# Pi-XO.net
KiCad netlist of a schematic drawn in EAGLE
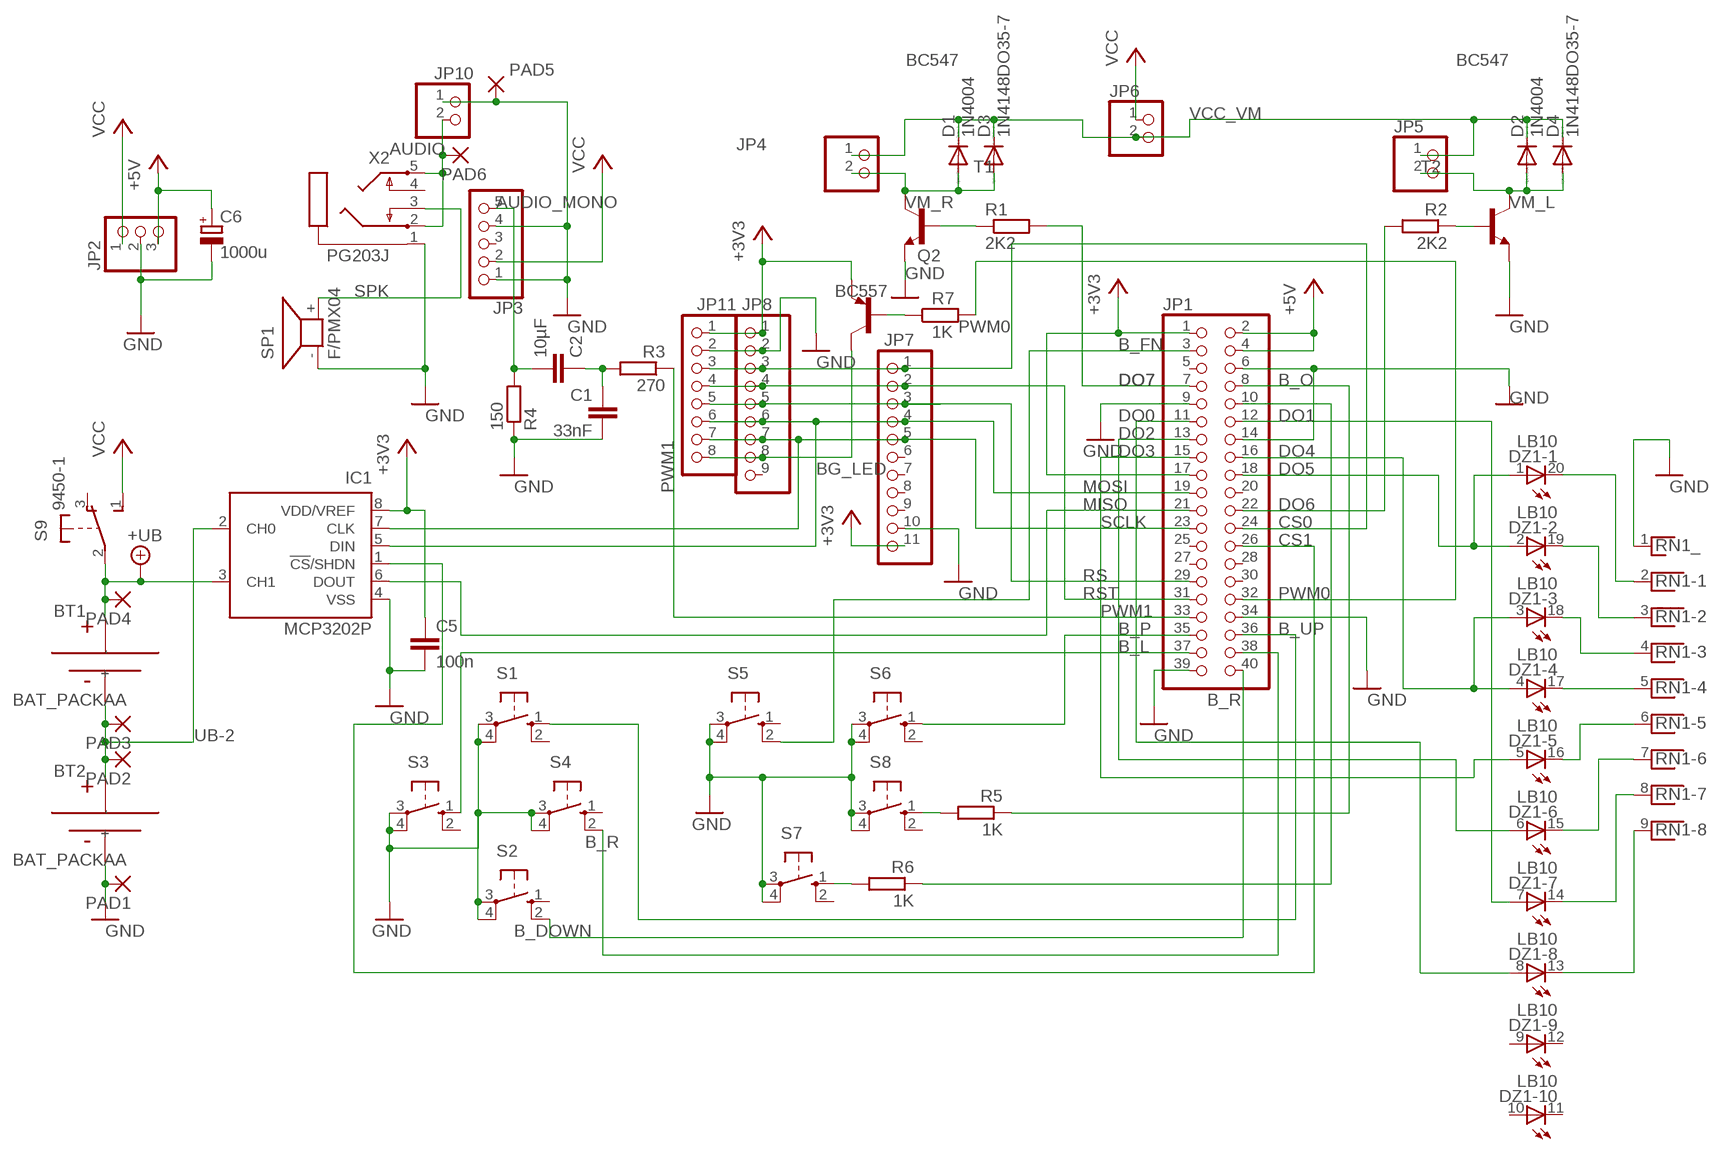
[diagram p0: schematic, sheet 1]

(export (version "E")
  (design (tool "Eeschema 10.0.6"))
  (components
    (comp (ref "BT1")
      (value "BAT_PACKAA")
      (footprint "eagle-import:BHAA-3")
      (fields (field (name "MANUFACTURER") "MPD") (field (name "MPN") "BHAA-3"))
      (libsource (lib "eagle-import") (part "BAT_PACKAA"))
    )
    (comp (ref "BT2")
      (value "BAT_PACKAA")
      (footprint "eagle-import:BHAA-3")
      (fields (field (name "MANUFACTURER") "MPD") (field (name "MPN") "BHAA-3"))
      (libsource (lib "eagle-import") (part "BAT_PACKAA"))
    )
    (comp (ref "C1")
      (value "33nF")
      (footprint "eagle-import:C050-024X044")
      (libsource (lib "eagle-import") (part "C-EU050-024X044"))
    )
    (comp (ref "C2")
      (value "10µF")
      (footprint "eagle-import:C050-024X044")
      (libsource (lib "eagle-import") (part "C-EU050-024X044"))
    )
    (comp (ref "C5")
      (value "100n")
      (footprint "eagle-import:C025-030X050")
      (libsource (lib "eagle-import") (part "C-EU025-030X050"))
    )
    (comp (ref "C6")
      (value "1000u")
      (footprint "eagle-import:B45181A")
      (libsource (lib "eagle-import") (part "CPOL-EUB45181A"))
    )
    (comp (ref "D1")
      (value "1N4004")
      (footprint "eagle-import:DO41-10")
      (libsource (lib "eagle-import") (part "1N4004"))
    )
    (comp (ref "D2")
      (value "1N4004")
      (footprint "eagle-import:DO41-10")
      (libsource (lib "eagle-import") (part "1N4004"))
    )
    (comp (ref "D3")
      (value "1N4148DO35-7")
      (footprint "eagle-import:DO35-7")
      (libsource (lib "eagle-import") (part "1N4148DO35-7"))
    )
    (comp (ref "D4")
      (value "1N4148DO35-7")
      (footprint "eagle-import:DO35-7")
      (libsource (lib "eagle-import") (part "1N4148DO35-7"))
    )
    (comp (ref "DZ1")
      (value "LB10")
      (footprint "eagle-import:LB10")
      (libsource (lib "eagle-import") (part "LB10"))
    )
    (comp (ref "IC1")
      (value "MCP3202P")
      (footprint "eagle-import:DIL8")
      (fields (field (name "MF") "MICROCHIP") (field (name "MPN") "MCP3202-CI/P"))
      (libsource (lib "eagle-import") (part "MCP3202P"))
    )
    (comp (ref "JP1")
      (value "PINHD-2X20")
      (footprint "eagle-import:2X20")
      (libsource (lib "eagle-import") (part "PINHD-2X20"))
    )
    (comp (ref "JP2")
      (value "PINHD-1X3")
      (footprint "eagle-import:1X03")
      (libsource (lib "eagle-import") (part "PINHD-1X3"))
    )
    (comp (ref "JP3")
      (value "PINHD-1X5")
      (footprint "eagle-import:1X05")
      (libsource (lib "eagle-import") (part "PINHD-1X5"))
    )
    (comp (ref "JP4")
      (value "PINHD-1X2")
      (footprint "eagle-import:1X02")
      (libsource (lib "eagle-import") (part "PINHD-1X2"))
    )
    (comp (ref "JP5")
      (value "PINHD-1X2")
      (footprint "eagle-import:1X02")
      (libsource (lib "eagle-import") (part "PINHD-1X2"))
    )
    (comp (ref "JP6")
      (value "PINHD-1X2")
      (footprint "eagle-import:1X02")
      (libsource (lib "eagle-import") (part "PINHD-1X2"))
    )
    (comp (ref "JP7")
      (value "PINHD-1X11")
      (footprint "eagle-import:1X11")
      (libsource (lib "eagle-import") (part "PINHD-1X11"))
    )
    (comp (ref "JP8")
      (value "PINHD-1X9")
      (footprint "eagle-import:1X09")
      (libsource (lib "eagle-import") (part "PINHD-1X9"))
    )
    (comp (ref "JP10")
      (value "PINHD-1X2")
      (footprint "eagle-import:1X02")
      (libsource (lib "eagle-import") (part "PINHD-1X2"))
    )
    (comp (ref "JP11")
      (value "PINHD-1X8")
      (footprint "eagle-import:1X08")
      (libsource (lib "eagle-import") (part "PINHD-1X8"))
    )
    (comp (ref "PAD1")
      (value "3,81/1,4")
      (footprint "eagle-import:3,81_1,4")
      (libsource (lib "eagle-import") (part "3,81/1,4"))
    )
    (comp (ref "PAD2")
      (value "3,81/1,4")
      (footprint "eagle-import:3,81_1,4")
      (libsource (lib "eagle-import") (part "3,81/1,4"))
    )
    (comp (ref "PAD3")
      (value "3,81/1,4")
      (footprint "eagle-import:3,81_1,4")
      (libsource (lib "eagle-import") (part "3,81/1,4"))
    )
    (comp (ref "PAD4")
      (value "3,81/1,4")
      (footprint "eagle-import:3,81_1,4")
      (libsource (lib "eagle-import") (part "3,81/1,4"))
    )
    (comp (ref "PAD5")
      (value "2,15/1,0")
      (footprint "eagle-import:2,15_1,0")
      (libsource (lib "eagle-import") (part "2,15/1,0"))
    )
    (comp (ref "PAD6")
      (value "2,15/1,0")
      (footprint "eagle-import:2,15_1,0")
      (libsource (lib "eagle-import") (part "2,15/1,0"))
    )
    (comp (ref "Q2")
      (value "BC557")
      (footprint "eagle-import:TO92")
      (libsource (lib "eagle-import") (part "BC557"))
    )
    (comp (ref "R1")
      (value "2K2")
      (footprint "eagle-import:0204_7")
      (libsource (lib "eagle-import") (part "R-EU_0204/7"))
    )
    (comp (ref "R2")
      (value "2K2")
      (footprint "eagle-import:0204_7")
      (libsource (lib "eagle-import") (part "R-EU_0204/7"))
    )
    (comp (ref "R3")
      (value "270")
      (footprint "eagle-import:0204_7")
      (libsource (lib "eagle-import") (part "R-EU_0204/7"))
    )
    (comp (ref "R4")
      (value "150")
      (footprint "eagle-import:0204_7")
      (libsource (lib "eagle-import") (part "R-EU_0204/7"))
    )
    (comp (ref "R5")
      (value "1K")
      (footprint "eagle-import:0204_7")
      (libsource (lib "eagle-import") (part "R-EU_0204/7"))
    )
    (comp (ref "R6")
      (value "1K")
      (footprint "eagle-import:0204_7")
      (libsource (lib "eagle-import") (part "R-EU_0204/7"))
    )
    (comp (ref "R7")
      (value "1K")
      (footprint "eagle-import:0204_7")
      (libsource (lib "eagle-import") (part "R-EU_0204/7"))
    )
    (comp (ref "RN1")
      (value "RNX8")
      (footprint "eagle-import:RN-9")
      (libsource (lib "eagle-import") (part "RNX8"))
    )
    (comp (ref "S1")
      (value "10-XX")
      (footprint "eagle-import:B3F-10XX")
      (fields (field (name "MPN") "B3F-1000"))
      (libsource (lib "eagle-import") (part "10-XX"))
    )
    (comp (ref "S2")
      (value "10-XX")
      (footprint "eagle-import:B3F-10XX")
      (fields (field (name "MPN") "B3F-1000"))
      (libsource (lib "eagle-import") (part "10-XX"))
    )
    (comp (ref "S3")
      (value "10-XX")
      (footprint "eagle-import:B3F-10XX")
      (fields (field (name "MPN") "B3F-1000"))
      (libsource (lib "eagle-import") (part "10-XX"))
    )
    (comp (ref "S4")
      (value "10-XX")
      (footprint "eagle-import:B3F-10XX")
      (fields (field (name "MPN") "B3F-1000"))
      (libsource (lib "eagle-import") (part "10-XX"))
    )
    (comp (ref "S5")
      (value "10-XX")
      (footprint "eagle-import:B3F-10XX")
      (fields (field (name "MPN") "B3F-1000"))
      (libsource (lib "eagle-import") (part "10-XX"))
    )
    (comp (ref "S6")
      (value "10-XX")
      (footprint "eagle-import:B3F-10XX")
      (fields (field (name "MPN") "B3F-1000"))
      (libsource (lib "eagle-import") (part "10-XX"))
    )
    (comp (ref "S7")
      (value "10-XX")
      (footprint "eagle-import:B3F-10XX")
      (fields (field (name "MPN") "B3F-1000"))
      (libsource (lib "eagle-import") (part "10-XX"))
    )
    (comp (ref "S8")
      (value "10-XX")
      (footprint "eagle-import:B3F-10XX")
      (fields (field (name "MPN") "B3F-1000"))
      (libsource (lib "eagle-import") (part "10-XX"))
    )
    (comp (ref "S9")
      (value "9450-1")
      (footprint "eagle-import:9450-1")
      (libsource (lib "eagle-import") (part "9450-1"))
    )
    (comp (ref "SP1")
      (value "F/PMX04")
      (footprint "eagle-import:F_PMX04A")
      (libsource (lib "eagle-import") (part "F/PMX04"))
    )
    (comp (ref "T1")
      (value "BC547")
      (footprint "eagle-import:TO92")
      (libsource (lib "eagle-import") (part "BC547"))
    )
    (comp (ref "T2")
      (value "BC547")
      (footprint "eagle-import:TO92")
      (libsource (lib "eagle-import") (part "BC547"))
    )
    (comp (ref "X2")
      (value "PG203J")
      (footprint "eagle-import:PG203J")
      (libsource (lib "eagle-import") (part "PG203J"))
    )
  )
  (nets
    (net (code "1") (name "+3V3") (class "Default")
      (node (ref "C5") (pin "1") (pinfunction "1_1") (pintype "passive"))
      (node (ref "IC1") (pin "8") (pinfunction "VDD/VREF_8") (pintype "input"))
      (node (ref "JP1") (pin "1") (pinfunction "1_1") (pintype "passive"))
      (node (ref "JP1") (pin "17") (pinfunction "17_17") (pintype "passive"))
      (node (ref "JP11") (pin "1") (pinfunction "1_1") (pintype "passive"))
      (node (ref "JP7") (pin "11") (pinfunction "11_11") (pintype "passive"))
      (node (ref "JP8") (pin "1") (pinfunction "1_1") (pintype "passive"))
      (node (ref "Q2") (pin "1") (pinfunction "E_1") (pintype "passive"))
    )
    (net (code "2") (name "+5V") (class "Default")
      (node (ref "C6") (pin "+") (pinfunction "+_+") (pintype "passive"))
      (node (ref "JP1") (pin "2") (pinfunction "2_2") (pintype "passive"))
      (node (ref "JP1") (pin "4") (pinfunction "4_4") (pintype "passive"))
      (node (ref "JP2") (pin "3") (pinfunction "3_3") (pintype "passive"))
    )
    (net (code "3") (name "+UB") (class "Default")
      (node (ref "BT1") (pin "+") (pinfunction "+_+") (pintype "bidirectional"))
      (node (ref "IC1") (pin "3") (pinfunction "CH1_3") (pintype "input"))
      (node (ref "PAD4") (pin "1") (pinfunction "P_1") (pintype "passive"))
      (node (ref "S9") (pin "2") (pinfunction "P_2") (pintype "passive"))
    )
    (net (code "4") (name "/AUDIO") (class "Default")
      (node (ref "JP10") (pin "2") (pinfunction "2_2") (pintype "passive"))
      (node (ref "PAD6") (pin "1") (pinfunction "P_1") (pintype "passive"))
      (node (ref "X2") (pin "2") (pinfunction "2_2") (pintype "passive"))
      (node (ref "X2") (pin "5") (pinfunction "5_5") (pintype "passive"))
    )
    (net (code "5") (name "/AUDIO_MONO") (class "Default")
      (node (ref "C2") (pin "2") (pinfunction "2_2") (pintype "passive"))
      (node (ref "JP3") (pin "5") (pinfunction "5_5") (pintype "passive"))
      (node (ref "R4") (pin "2") (pinfunction "2_2") (pintype "passive"))
    )
    (net (code "6") (name "/BG_LED") (class "Default")
      (node (ref "JP11") (pin "8") (pinfunction "8_8") (pintype "passive"))
      (node (ref "JP8") (pin "8") (pinfunction "8_8") (pintype "passive"))
      (node (ref "Q2") (pin "3") (pinfunction "C_3") (pintype "passive"))
    )
    (net (code "7") (name "/B_DOWN") (class "Default")
      (node (ref "JP1") (pin "40") (pinfunction "40_40") (pintype "passive"))
      (node (ref "S2") (pin "2") (pinfunction "S1_2") (pintype "passive"))
    )
    (net (code "8") (name "/B_FN") (class "Default")
      (node (ref "JP1") (pin "3") (pinfunction "3_3") (pintype "passive"))
      (node (ref "S5") (pin "2") (pinfunction "S1_2") (pintype "passive"))
    )
    (net (code "9") (name "/B_L") (class "Default")
      (node (ref "JP1") (pin "37") (pinfunction "37_37") (pintype "passive"))
      (node (ref "S3") (pin "1") (pinfunction "S_1") (pintype "passive"))
    )
    (net (code "10") (name "/B_O") (class "Default")
      (node (ref "JP1") (pin "8") (pinfunction "8_8") (pintype "passive"))
      (node (ref "R5") (pin "1") (pinfunction "1_1") (pintype "passive"))
    )
    (net (code "11") (name "/B_P") (class "Default")
      (node (ref "JP1") (pin "35") (pinfunction "35_35") (pintype "passive"))
      (node (ref "S6") (pin "1") (pinfunction "S_1") (pintype "passive"))
    )
    (net (code "12") (name "/B_R") (class "Default")
      (node (ref "JP1") (pin "38") (pinfunction "38_38") (pintype "passive"))
      (node (ref "S4") (pin "2") (pinfunction "S1_2") (pintype "passive"))
    )
    (net (code "13") (name "/B_UP") (class "Default")
      (node (ref "JP1") (pin "36") (pinfunction "36_36") (pintype "passive"))
      (node (ref "S1") (pin "1") (pinfunction "S_1") (pintype "passive"))
    )
    (net (code "14") (name "/CS0") (class "Default")
      (node (ref "JP1") (pin "24") (pinfunction "24_24") (pintype "passive"))
      (node (ref "JP11") (pin "3") (pinfunction "3_3") (pintype "passive"))
      (node (ref "JP7") (pin "1") (pinfunction "1_1") (pintype "passive"))
      (node (ref "JP8") (pin "3") (pinfunction "3_3") (pintype "passive"))
    )
    (net (code "15") (name "/CS1") (class "Default")
      (node (ref "IC1") (pin "1") (pinfunction "~{CS}/SHDN_1") (pintype "input"))
      (node (ref "JP1") (pin "26") (pinfunction "26_26") (pintype "passive"))
    )
    (net (code "16") (name "/DO0") (class "Default")
      (node (ref "DZ1") (pin "8") (pinfunction "A_8") (pintype "passive"))
      (node (ref "JP1") (pin "11") (pinfunction "11_11") (pintype "passive"))
    )
    (net (code "17") (name "/DO1") (class "Default")
      (node (ref "DZ1") (pin "7") (pinfunction "A_7") (pintype "passive"))
      (node (ref "JP1") (pin "12") (pinfunction "12_12") (pintype "passive"))
    )
    (net (code "18") (name "/DO2") (class "Default")
      (node (ref "DZ1") (pin "6") (pinfunction "A_6") (pintype "passive"))
      (node (ref "JP1") (pin "13") (pinfunction "13_13") (pintype "passive"))
    )
    (net (code "19") (name "/DO3") (class "Default")
      (node (ref "DZ1") (pin "5") (pinfunction "A_5") (pintype "passive"))
      (node (ref "JP1") (pin "15") (pinfunction "15_15") (pintype "passive"))
    )
    (net (code "20") (name "/DO4") (class "Default")
      (node (ref "DZ1") (pin "3") (pinfunction "A_3") (pintype "passive"))
      (node (ref "DZ1") (pin "4") (pinfunction "A_4") (pintype "passive"))
      (node (ref "JP1") (pin "16") (pinfunction "16_16") (pintype "passive"))
    )
    (net (code "21") (name "/DO5") (class "Default")
      (node (ref "DZ1") (pin "1") (pinfunction "A_1") (pintype "passive"))
      (node (ref "DZ1") (pin "2") (pinfunction "A_2") (pintype "passive"))
      (node (ref "JP1") (pin "18") (pinfunction "18_18") (pintype "passive"))
    )
    (net (code "22") (name "/DO6") (class "Default")
      (node (ref "JP1") (pin "22") (pinfunction "22_22") (pintype "passive"))
      (node (ref "R2") (pin "2") (pinfunction "2_2") (pintype "passive"))
    )
    (net (code "23") (name "/DO7") (class "Default")
      (node (ref "JP1") (pin "7") (pinfunction "7_7") (pintype "passive"))
      (node (ref "R1") (pin "2") (pinfunction "2_2") (pintype "passive"))
    )
    (net (code "24") (name "/MISO") (class "Default")
      (node (ref "IC1") (pin "6") (pinfunction "DOUT_6") (pintype "input"))
      (node (ref "JP1") (pin "21") (pinfunction "21_21") (pintype "passive"))
    )
    (net (code "25") (name "/MOSI") (class "Default")
      (node (ref "IC1") (pin "5") (pinfunction "DIN_5") (pintype "input"))
      (node (ref "JP1") (pin "19") (pinfunction "19_19") (pintype "passive"))
      (node (ref "JP11") (pin "6") (pinfunction "6_6") (pintype "passive"))
      (node (ref "JP7") (pin "4") (pinfunction "4_4") (pintype "passive"))
      (node (ref "JP8") (pin "6") (pinfunction "6_6") (pintype "passive"))
    )
    (net (code "26") (name "/PWM0") (class "Default")
      (node (ref "JP1") (pin "32") (pinfunction "32_32") (pintype "passive"))
      (node (ref "R7") (pin "2") (pinfunction "2_2") (pintype "passive"))
    )
    (net (code "27") (name "/PWM1") (class "Default")
      (node (ref "JP1") (pin "33") (pinfunction "33_33") (pintype "passive"))
      (node (ref "R3") (pin "1") (pinfunction "1_1") (pintype "passive"))
    )
    (net (code "28") (name "/RS") (class "Default")
      (node (ref "JP1") (pin "29") (pinfunction "29_29") (pintype "passive"))
      (node (ref "JP11") (pin "5") (pinfunction "5_5") (pintype "passive"))
      (node (ref "JP7") (pin "3") (pinfunction "3_3") (pintype "passive"))
      (node (ref "JP8") (pin "5") (pinfunction "5_5") (pintype "passive"))
    )
    (net (code "29") (name "/RST") (class "Default")
      (node (ref "JP1") (pin "31") (pinfunction "31_31") (pintype "passive"))
      (node (ref "JP11") (pin "4") (pinfunction "4_4") (pintype "passive"))
      (node (ref "JP7") (pin "2") (pinfunction "2_2") (pintype "passive"))
      (node (ref "JP8") (pin "4") (pinfunction "4_4") (pintype "passive"))
    )
    (net (code "30") (name "/SCLK") (class "Default")
      (node (ref "IC1") (pin "7") (pinfunction "CLK_7") (pintype "input"))
      (node (ref "JP1") (pin "23") (pinfunction "23_23") (pintype "passive"))
      (node (ref "JP11") (pin "7") (pinfunction "7_7") (pintype "passive"))
      (node (ref "JP7") (pin "5") (pinfunction "5_5") (pintype "passive"))
      (node (ref "JP8") (pin "7") (pinfunction "7_7") (pintype "passive"))
    )
    (net (code "31") (name "/SPK") (class "Default")
      (node (ref "SP1") (pin "+") (pinfunction "2_+") (pintype "passive"))
      (node (ref "X2") (pin "3") (pinfunction "3_3") (pintype "passive"))
    )
    (net (code "32") (name "/UB-2") (class "Default")
      (node (ref "BT1") (pin "-") (pinfunction "-_-") (pintype "bidirectional"))
      (node (ref "BT2") (pin "+") (pinfunction "+_+") (pintype "bidirectional"))
      (node (ref "IC1") (pin "2") (pinfunction "CH0_2") (pintype "input"))
      (node (ref "PAD2") (pin "1") (pinfunction "P_1") (pintype "passive"))
      (node (ref "PAD3") (pin "1") (pinfunction "P_1") (pintype "passive"))
    )
    (net (code "33") (name "/VCC_VM") (class "Default")
      (node (ref "D1") (pin "C") (pinfunction "C_C") (pintype "passive"))
      (node (ref "D2") (pin "C") (pinfunction "C_C") (pintype "passive"))
      (node (ref "D3") (pin "C") (pinfunction "C_C") (pintype "passive"))
      (node (ref "D4") (pin "C") (pinfunction "C_C") (pintype "passive"))
      (node (ref "JP4") (pin "1") (pinfunction "1_1") (pintype "passive"))
      (node (ref "JP5") (pin "1") (pinfunction "1_1") (pintype "passive"))
      (node (ref "JP6") (pin "2") (pinfunction "2_2") (pintype "passive"))
    )
    (net (code "34") (name "/VM_L") (class "Default")
      (node (ref "D2") (pin "A") (pinfunction "A_A") (pintype "passive"))
      (node (ref "D4") (pin "A") (pinfunction "A_A") (pintype "passive"))
      (node (ref "JP5") (pin "2") (pinfunction "2_2") (pintype "passive"))
      (node (ref "T2") (pin "3") (pinfunction "C_3") (pintype "passive"))
    )
    (net (code "35") (name "/VM_R") (class "Default")
      (node (ref "D1") (pin "A") (pinfunction "A_A") (pintype "passive"))
      (node (ref "D3") (pin "A") (pinfunction "A_A") (pintype "passive"))
      (node (ref "JP4") (pin "2") (pinfunction "2_2") (pintype "passive"))
      (node (ref "T1") (pin "3") (pinfunction "C_3") (pintype "passive"))
    )
    (net (code "36") (name "GND") (class "Default")
      (node (ref "BT2") (pin "-") (pinfunction "-_-") (pintype "bidirectional"))
      (node (ref "C1") (pin "2") (pinfunction "2_2") (pintype "passive"))
      (node (ref "C5") (pin "2") (pinfunction "2_2") (pintype "passive"))
      (node (ref "C6") (pin "-") (pinfunction "-_-") (pintype "passive"))
      (node (ref "IC1") (pin "4") (pinfunction "VSS_4") (pintype "input"))
      (node (ref "JP1") (pin "14") (pinfunction "14_14") (pintype "passive"))
      (node (ref "JP1") (pin "34") (pinfunction "34_34") (pintype "passive"))
      (node (ref "JP1") (pin "39") (pinfunction "39_39") (pintype "passive"))
      (node (ref "JP1") (pin "6") (pinfunction "6_6") (pintype "passive"))
      (node (ref "JP1") (pin "9") (pinfunction "9_9") (pintype "passive"))
      (node (ref "JP10") (pin "1") (pinfunction "1_1") (pintype "passive"))
      (node (ref "JP11") (pin "2") (pinfunction "2_2") (pintype "passive"))
      (node (ref "JP2") (pin "2") (pinfunction "2_2") (pintype "passive"))
      (node (ref "JP3") (pin "1") (pinfunction "1_1") (pintype "passive"))
      (node (ref "JP3") (pin "4") (pinfunction "4_4") (pintype "passive"))
      (node (ref "JP7") (pin "10") (pinfunction "10_10") (pintype "passive"))
      (node (ref "JP8") (pin "2") (pinfunction "2_2") (pintype "passive"))
      (node (ref "PAD1") (pin "1") (pinfunction "P_1") (pintype "passive"))
      (node (ref "PAD5") (pin "1") (pinfunction "P_1") (pintype "passive"))
      (node (ref "R4") (pin "1") (pinfunction "1_1") (pintype "passive"))
      (node (ref "RN1") (pin "1") (pinfunction "1_1") (pintype "passive"))
      (node (ref "S1") (pin "3") (pinfunction "P_3") (pintype "passive"))
      (node (ref "S1") (pin "4") (pinfunction "P1_4") (pintype "passive"))
      (node (ref "S2") (pin "3") (pinfunction "P_3") (pintype "passive"))
      (node (ref "S2") (pin "4") (pinfunction "P1_4") (pintype "passive"))
      (node (ref "S3") (pin "3") (pinfunction "P_3") (pintype "passive"))
      (node (ref "S3") (pin "4") (pinfunction "P1_4") (pintype "passive"))
      (node (ref "S4") (pin "3") (pinfunction "P_3") (pintype "passive"))
      (node (ref "S4") (pin "4") (pinfunction "P1_4") (pintype "passive"))
      (node (ref "S5") (pin "3") (pinfunction "P_3") (pintype "passive"))
      (node (ref "S5") (pin "4") (pinfunction "P1_4") (pintype "passive"))
      (node (ref "S6") (pin "3") (pinfunction "P_3") (pintype "passive"))
      (node (ref "S6") (pin "4") (pinfunction "P1_4") (pintype "passive"))
      (node (ref "S7") (pin "3") (pinfunction "P_3") (pintype "passive"))
      (node (ref "S7") (pin "4") (pinfunction "P1_4") (pintype "passive"))
      (node (ref "S8") (pin "3") (pinfunction "P_3") (pintype "passive"))
      (node (ref "S8") (pin "4") (pinfunction "P1_4") (pintype "passive"))
      (node (ref "SP1") (pin "-") (pinfunction "1_-") (pintype "passive"))
      (node (ref "T1") (pin "1") (pinfunction "E_1") (pintype "passive"))
      (node (ref "T2") (pin "1") (pinfunction "E_1") (pintype "passive"))
      (node (ref "X2") (pin "1") (pinfunction "1_1") (pintype "passive"))
    )
    (net (code "37") (name "Net-(C1-Pad1)") (class "Default")
      (node (ref "C1") (pin "1") (pinfunction "1_1") (pintype "passive"))
      (node (ref "C2") (pin "1") (pinfunction "1_1") (pintype "passive"))
      (node (ref "R3") (pin "2") (pinfunction "2_2") (pintype "passive"))
    )
    (net (code "38") (name "Net-(DZ1A-C)") (class "Default")
      (node (ref "DZ1") (pin "20") (pinfunction "C_20") (pintype "passive"))
      (node (ref "RN1") (pin "2") (pinfunction "1_2") (pintype "passive"))
    )
    (net (code "39") (name "Net-(DZ1C-C)") (class "Default")
      (node (ref "DZ1") (pin "19") (pinfunction "C_19") (pintype "passive"))
      (node (ref "RN1") (pin "3") (pinfunction "1_3") (pintype "passive"))
    )
    (net (code "40") (name "Net-(DZ1D-C)") (class "Default")
      (node (ref "DZ1") (pin "18") (pinfunction "C_18") (pintype "passive"))
      (node (ref "RN1") (pin "4") (pinfunction "1_4") (pintype "passive"))
    )
    (net (code "41") (name "Net-(DZ1E-C)") (class "Default")
      (node (ref "DZ1") (pin "17") (pinfunction "C_17") (pintype "passive"))
      (node (ref "RN1") (pin "5") (pinfunction "1_5") (pintype "passive"))
    )
    (net (code "42") (name "Net-(DZ1F-C)") (class "Default")
      (node (ref "DZ1") (pin "16") (pinfunction "C_16") (pintype "passive"))
      (node (ref "RN1") (pin "6") (pinfunction "1_6") (pintype "passive"))
    )
    (net (code "43") (name "Net-(DZ1G-C)") (class "Default")
      (node (ref "DZ1") (pin "15") (pinfunction "C_15") (pintype "passive"))
      (node (ref "RN1") (pin "7") (pinfunction "1_7") (pintype "passive"))
    )
    (net (code "44") (name "Net-(DZ1H-C)") (class "Default")
      (node (ref "DZ1") (pin "14") (pinfunction "C_14") (pintype "passive"))
      (node (ref "RN1") (pin "8") (pinfunction "1_8") (pintype "passive"))
    )
    (net (code "45") (name "Net-(DZ1I-C)") (class "Default")
      (node (ref "DZ1") (pin "13") (pinfunction "C_13") (pintype "passive"))
      (node (ref "RN1") (pin "9") (pinfunction "1_9") (pintype "passive"))
    )
    (net (code "46") (name "Net-(JP1-Pad10)") (class "Default")
      (node (ref "JP1") (pin "10") (pinfunction "10_10") (pintype "passive"))
      (node (ref "R6") (pin "1") (pinfunction "1_1") (pintype "passive"))
    )
    (net (code "47") (name "Net-(Q2-B)") (class "Default")
      (node (ref "Q2") (pin "2") (pinfunction "B_2") (pintype "passive"))
      (node (ref "R7") (pin "1") (pinfunction "1_1") (pintype "passive"))
    )
    (net (code "48") (name "Net-(S7-S)") (class "Default")
      (node (ref "R6") (pin "2") (pinfunction "2_2") (pintype "passive"))
      (node (ref "S7") (pin "1") (pinfunction "S_1") (pintype "passive"))
    )
    (net (code "49") (name "Net-(S8-S)") (class "Default")
      (node (ref "R5") (pin "2") (pinfunction "2_2") (pintype "passive"))
      (node (ref "S8") (pin "1") (pinfunction "S_1") (pintype "passive"))
    )
    (net (code "50") (name "Net-(T1-B)") (class "Default")
      (node (ref "R1") (pin "1") (pinfunction "1_1") (pintype "passive"))
      (node (ref "T1") (pin "2") (pinfunction "B_2") (pintype "passive"))
    )
    (net (code "51") (name "Net-(T2-B)") (class "Default")
      (node (ref "R2") (pin "1") (pinfunction "1_1") (pintype "passive"))
      (node (ref "T2") (pin "2") (pinfunction "B_2") (pintype "passive"))
    )
    (net (code "52") (name "VCC") (class "Default")
      (node (ref "JP2") (pin "1") (pinfunction "1_1") (pintype "passive"))
      (node (ref "JP3") (pin "2") (pinfunction "2_2") (pintype "passive"))
      (node (ref "JP6") (pin "1") (pinfunction "1_1") (pintype "passive"))
      (node (ref "S9") (pin "1") (pinfunction "S_1") (pintype "passive"))
    )
    (net (code "53") (name "unconnected-(DZ1B-A-Pad10)") (class "Default")
      (node (ref "DZ1") (pin "10") (pinfunction "A_10") (pintype "passive"))
    )
    (net (code "54") (name "unconnected-(DZ1B-C-Pad11)") (class "Default")
      (node (ref "DZ1") (pin "11") (pinfunction "C_11") (pintype "passive"))
    )
    (net (code "55") (name "unconnected-(DZ1J-A-Pad9)") (class "Default")
      (node (ref "DZ1") (pin "9") (pinfunction "A_9") (pintype "passive"))
    )
    (net (code "56") (name "unconnected-(DZ1J-C-Pad12)") (class "Default")
      (node (ref "DZ1") (pin "12") (pinfunction "C_12") (pintype "passive"))
    )
    (net (code "57") (name "unconnected-(JP1-Pad5)") (class "Default")
      (node (ref "JP1") (pin "5") (pinfunction "5_5") (pintype "passive"))
    )
    (net (code "58") (name "unconnected-(JP1-Pad20)") (class "Default")
      (node (ref "JP1") (pin "20") (pinfunction "20_20") (pintype "passive"))
    )
    (net (code "59") (name "unconnected-(JP1-Pad25)") (class "Default")
      (node (ref "JP1") (pin "25") (pinfunction "25_25") (pintype "passive"))
    )
    (net (code "60") (name "unconnected-(JP1-Pad27)") (class "Default")
      (node (ref "JP1") (pin "27") (pinfunction "27_27") (pintype "passive"))
    )
    (net (code "61") (name "unconnected-(JP1-Pad28)") (class "Default")
      (node (ref "JP1") (pin "28") (pinfunction "28_28") (pintype "passive"))
    )
    (net (code "62") (name "unconnected-(JP1-Pad30)") (class "Default")
      (node (ref "JP1") (pin "30") (pinfunction "30_30") (pintype "passive"))
    )
    (net (code "63") (name "unconnected-(JP3-Pad3)") (class "Default")
      (node (ref "JP3") (pin "3") (pinfunction "3_3") (pintype "passive"))
    )
    (net (code "64") (name "unconnected-(JP7-Pad6)") (class "Default")
      (node (ref "JP7") (pin "6") (pinfunction "6_6") (pintype "passive"))
    )
    (net (code "65") (name "unconnected-(JP7-Pad7)") (class "Default")
      (node (ref "JP7") (pin "7") (pinfunction "7_7") (pintype "passive"))
    )
    (net (code "66") (name "unconnected-(JP7-Pad8)") (class "Default")
      (node (ref "JP7") (pin "8") (pinfunction "8_8") (pintype "passive"))
    )
    (net (code "67") (name "unconnected-(JP7-Pad9)") (class "Default")
      (node (ref "JP7") (pin "9") (pinfunction "9_9") (pintype "passive"))
    )
    (net (code "68") (name "unconnected-(JP8-Pad9)") (class "Default")
      (node (ref "JP8") (pin "9") (pinfunction "9_9") (pintype "passive"))
    )
    (net (code "69") (name "unconnected-(S1-S1-Pad2)") (class "Default")
      (node (ref "S1") (pin "2") (pinfunction "S1_2") (pintype "passive"))
    )
    (net (code "70") (name "unconnected-(S2-S-Pad1)") (class "Default")
      (node (ref "S2") (pin "1") (pinfunction "S_1") (pintype "passive"))
    )
    (net (code "71") (name "unconnected-(S3-S1-Pad2)") (class "Default")
      (node (ref "S3") (pin "2") (pinfunction "S1_2") (pintype "passive"))
    )
    (net (code "72") (name "unconnected-(S4-S-Pad1)") (class "Default")
      (node (ref "S4") (pin "1") (pinfunction "S_1") (pintype "passive"))
    )
    (net (code "73") (name "unconnected-(S5-S-Pad1)") (class "Default")
      (node (ref "S5") (pin "1") (pinfunction "S_1") (pintype "passive"))
    )
    (net (code "74") (name "unconnected-(S6-S1-Pad2)") (class "Default")
      (node (ref "S6") (pin "2") (pinfunction "S1_2") (pintype "passive"))
    )
    (net (code "75") (name "unconnected-(S7-S1-Pad2)") (class "Default")
      (node (ref "S7") (pin "2") (pinfunction "S1_2") (pintype "passive"))
    )
    (net (code "76") (name "unconnected-(S8-S1-Pad2)") (class "Default")
      (node (ref "S8") (pin "2") (pinfunction "S1_2") (pintype "passive"))
    )
    (net (code "77") (name "unconnected-(S9-O-Pad3)") (class "Default")
      (node (ref "S9") (pin "3") (pinfunction "O_3") (pintype "passive"))
    )
    (net (code "78") (name "unconnected-(X2-Pad4)") (class "Default")
      (node (ref "X2") (pin "4") (pinfunction "4_4") (pintype "passive"))
    )
  )
)
